# charge_controller.net
KiCad netlist of a schematic drawn in EAGLE
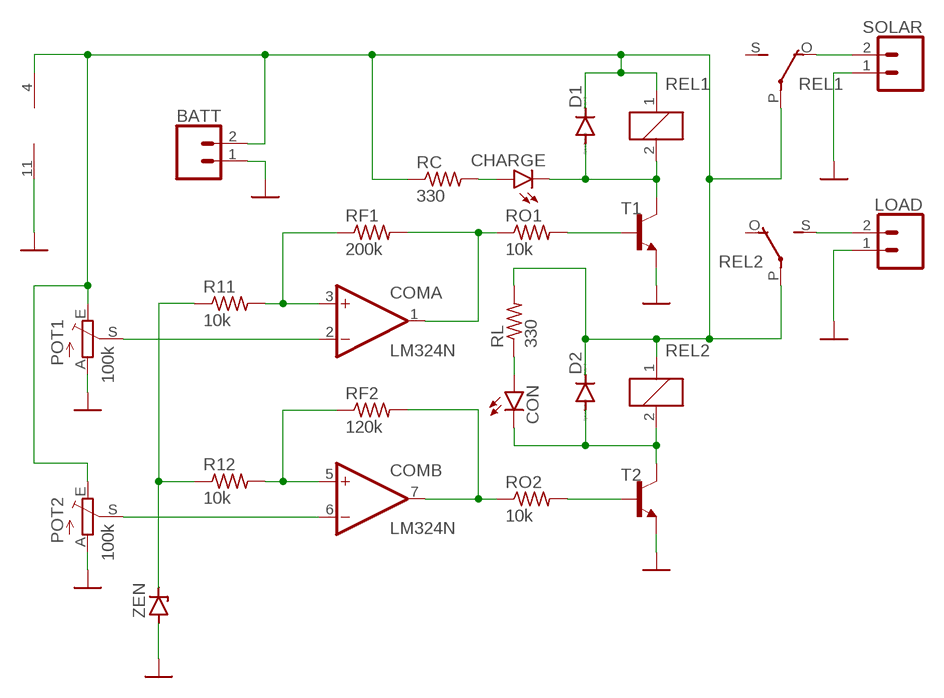
[diagram p0: schematic, sheet 1]

(export (version "E")
  (design (tool "Eeschema 10.0.6"))
  (components
    (comp (ref "BATT")
      (value "CONN_02PTH4")
      (footprint "eagle-import:1X02_XTRA_BIG")
      (libsource (lib "eagle-import") (part "CONN_02PTH4"))
    )
    (comp (ref "CHARGE")
      (value "LED5MM")
      (footprint "eagle-import:LED5MM")
      (libsource (lib "eagle-import") (part "LED5MM"))
    )
    (comp (ref "COM")
      (value "LM324N")
      (footprint "eagle-import:DIL14")
      (libsource (lib "eagle-import") (part "LM324N"))
    )
    (comp (ref "CON")
      (value "LED5MM")
      (footprint "eagle-import:LED5MM")
      (libsource (lib "eagle-import") (part "LED5MM"))
    )
    (comp (ref "D1")
      (value "1N4148DO35-7")
      (footprint "eagle-import:DO35-7")
      (libsource (lib "eagle-import") (part "1N4148DO35-7"))
    )
    (comp (ref "D2")
      (value "1N4148DO35-7")
      (footprint "eagle-import:DO35-7")
      (libsource (lib "eagle-import") (part "1N4148DO35-7"))
    )
    (comp (ref "LOAD")
      (value "CONN_02PTH4")
      (footprint "eagle-import:1X02_XTRA_BIG")
      (libsource (lib "eagle-import") (part "CONN_02PTH4"))
    )
    (comp (ref "POT1")
      (value "100k")
      (footprint "eagle-import:CT6")
      (libsource (lib "eagle-import") (part "TRIM_EU-CT6"))
    )
    (comp (ref "POT2")
      (value "100k")
      (footprint "eagle-import:CT6")
      (libsource (lib "eagle-import") (part "TRIM_EU-CT6"))
    )
    (comp (ref "R11")
      (value "10k")
      (footprint "eagle-import:0207_10")
      (libsource (lib "eagle-import") (part "R-US_0207/10"))
    )
    (comp (ref "R12")
      (value "10k")
      (footprint "eagle-import:0207_10")
      (libsource (lib "eagle-import") (part "R-US_0207/10"))
    )
    (comp (ref "RC")
      (value "330")
      (footprint "eagle-import:0207_10")
      (libsource (lib "eagle-import") (part "R-US_0207/10"))
    )
    (comp (ref "REL1")
      (value "G5L")
      (footprint "eagle-import:G5LE")
      (libsource (lib "eagle-import") (part "G5L"))
    )
    (comp (ref "REL2")
      (value "G5L")
      (footprint "eagle-import:G5LE")
      (libsource (lib "eagle-import") (part "G5L"))
    )
    (comp (ref "RF1")
      (value "200k")
      (footprint "eagle-import:0207_10")
      (libsource (lib "eagle-import") (part "R-US_0207/10"))
    )
    (comp (ref "RF2")
      (value "120k")
      (footprint "eagle-import:0207_10")
      (libsource (lib "eagle-import") (part "R-US_0207/10"))
    )
    (comp (ref "RL")
      (value "330")
      (footprint "eagle-import:0207_10")
      (libsource (lib "eagle-import") (part "R-US_0207/10"))
    )
    (comp (ref "RO1")
      (value "10k")
      (footprint "eagle-import:0207_10")
      (libsource (lib "eagle-import") (part "R-US_0207/10"))
    )
    (comp (ref "RO2")
      (value "10k")
      (footprint "eagle-import:0207_10")
      (libsource (lib "eagle-import") (part "R-US_0207/10"))
    )
    (comp (ref "SOLAR")
      (value "CONN_02PTH4")
      (footprint "eagle-import:1X02_XTRA_BIG")
      (libsource (lib "eagle-import") (part "CONN_02PTH4"))
    )
    (comp (ref "T1")
      (value "MPS2222A-NPN-TO92-CBE")
      (footprint "eagle-import:TO92-CBE")
      (libsource (lib "eagle-import") (part "-NPN-TO92-CBEMPS2222A"))
    )
    (comp (ref "T2")
      (value "MPS2222A-NPN-TO92-CBE")
      (footprint "eagle-import:TO92-CBE")
      (libsource (lib "eagle-import") (part "-NPN-TO92-CBEMPS2222A"))
    )
    (comp (ref "ZEN")
      (value "BZD23")
      (footprint "eagle-import:SOD81")
      (libsource (lib "eagle-import") (part "BZD23"))
    )
  )
  (nets
    (net (code "1") (name "GND") (class "Default")
      (node (ref "BATT") (pin "1") (pinfunction "1_1") (pintype "passive"))
      (node (ref "COM") (pin "11") (pinfunction "V-_11") (pintype "power_in"))
      (node (ref "LOAD") (pin "1") (pinfunction "1_1") (pintype "passive"))
      (node (ref "POT1") (pin "A") (pinfunction "A_A") (pintype "passive"))
      (node (ref "POT2") (pin "A") (pinfunction "A_A") (pintype "passive"))
      (node (ref "SOLAR") (pin "1") (pinfunction "1_1") (pintype "passive"))
      (node (ref "T1") (pin "E") (pinfunction "E_E") (pintype "passive"))
      (node (ref "T2") (pin "E") (pinfunction "E_E") (pintype "passive"))
      (node (ref "ZEN") (pin "A") (pinfunction "A_A") (pintype "passive"))
    )
    (net (code "2") (name "Net-(CHARGE-C)") (class "Default")
      (node (ref "CHARGE") (pin "K") (pinfunction "C_K") (pintype "passive"))
      (node (ref "D1") (pin "A") (pinfunction "A_A") (pintype "passive"))
      (node (ref "REL1") (pin "2") (pinfunction "2_2") (pintype "passive"))
      (node (ref "T1") (pin "C") (pinfunction "C_C") (pintype "passive"))
    )
    (net (code "3") (name "Net-(CHARGE-PadA)") (class "Default")
      (node (ref "CHARGE") (pin "A") (pinfunction "A_A") (pintype "passive"))
      (node (ref "RC") (pin "2") (pinfunction "2_2") (pintype "passive"))
    )
    (net (code "4") (name "Net-(COMA-+IN)") (class "Default")
      (node (ref "COM") (pin "3") (pinfunction "+IN_3") (pintype "input"))
      (node (ref "R11") (pin "2") (pinfunction "2_2") (pintype "passive"))
      (node (ref "RF1") (pin "1") (pinfunction "1_1") (pintype "passive"))
    )
    (net (code "5") (name "Net-(COMA--IN)") (class "Default")
      (node (ref "COM") (pin "2") (pinfunction "-IN_2") (pintype "input"))
      (node (ref "POT1") (pin "S") (pinfunction "S_S") (pintype "passive"))
    )
    (net (code "6") (name "Net-(COMA-OUT)") (class "Default")
      (node (ref "COM") (pin "1") (pinfunction "OUT_1") (pintype "output"))
      (node (ref "RF1") (pin "2") (pinfunction "2_2") (pintype "passive"))
      (node (ref "RO1") (pin "1") (pinfunction "1_1") (pintype "passive"))
    )
    (net (code "7") (name "Net-(COMB-+IN)") (class "Default")
      (node (ref "COM") (pin "5") (pinfunction "+IN_5") (pintype "input"))
      (node (ref "R12") (pin "2") (pinfunction "2_2") (pintype "passive"))
      (node (ref "RF2") (pin "1") (pinfunction "1_1") (pintype "passive"))
    )
    (net (code "8") (name "Net-(COMB--IN)") (class "Default")
      (node (ref "COM") (pin "6") (pinfunction "-IN_6") (pintype "input"))
      (node (ref "POT2") (pin "S") (pinfunction "S_S") (pintype "passive"))
    )
    (net (code "9") (name "Net-(COMB-OUT)") (class "Default")
      (node (ref "COM") (pin "7") (pinfunction "OUT_7") (pintype "output"))
      (node (ref "RF2") (pin "2") (pinfunction "2_2") (pintype "passive"))
      (node (ref "RO2") (pin "1") (pinfunction "1_1") (pintype "passive"))
    )
    (net (code "10") (name "Net-(COME-V+)") (class "Default")
      (node (ref "BATT") (pin "2") (pinfunction "2_2") (pintype "passive"))
      (node (ref "COM") (pin "4") (pinfunction "V+_4") (pintype "power_in"))
      (node (ref "D1") (pin "C") (pinfunction "C_C") (pintype "passive"))
      (node (ref "D2") (pin "C") (pinfunction "C_C") (pintype "passive"))
      (node (ref "POT1") (pin "E") (pinfunction "E_E") (pintype "passive"))
      (node (ref "POT2") (pin "E") (pinfunction "E_E") (pintype "passive"))
      (node (ref "RC") (pin "1") (pinfunction "1_1") (pintype "passive"))
      (node (ref "REL1") (pin "1") (pinfunction "1_1") (pintype "passive"))
      (node (ref "REL1") (pin "P") (pinfunction "P_P") (pintype "passive"))
      (node (ref "REL2") (pin "1") (pinfunction "1_1") (pintype "passive"))
      (node (ref "REL2") (pin "P") (pinfunction "P_P") (pintype "passive"))
      (node (ref "RL") (pin "2") (pinfunction "2_2") (pintype "passive"))
    )
    (net (code "11") (name "Net-(CON-C)") (class "Default")
      (node (ref "CON") (pin "K") (pinfunction "C_K") (pintype "passive"))
      (node (ref "D2") (pin "A") (pinfunction "A_A") (pintype "passive"))
      (node (ref "REL2") (pin "2") (pinfunction "2_2") (pintype "passive"))
      (node (ref "T2") (pin "C") (pinfunction "C_C") (pintype "passive"))
    )
    (net (code "12") (name "Net-(CON-PadA)") (class "Default")
      (node (ref "CON") (pin "A") (pinfunction "A_A") (pintype "passive"))
      (node (ref "RL") (pin "1") (pinfunction "1_1") (pintype "passive"))
    )
    (net (code "13") (name "Net-(LOAD-Pad2)") (class "Default")
      (node (ref "LOAD") (pin "2") (pinfunction "2_2") (pintype "passive"))
      (node (ref "REL2") (pin "S") (pinfunction "S_S") (pintype "passive"))
    )
    (net (code "14") (name "Net-(R11-Pad1)") (class "Default")
      (node (ref "R11") (pin "1") (pinfunction "1_1") (pintype "passive"))
      (node (ref "R12") (pin "1") (pinfunction "1_1") (pintype "passive"))
      (node (ref "ZEN") (pin "C") (pinfunction "C_C") (pintype "passive"))
    )
    (net (code "15") (name "Net-(REL1-PadO)") (class "Default")
      (node (ref "REL1") (pin "O") (pinfunction "O_O") (pintype "passive"))
      (node (ref "SOLAR") (pin "2") (pinfunction "2_2") (pintype "passive"))
    )
    (net (code "16") (name "Net-(RO1-Pad2)") (class "Default")
      (node (ref "RO1") (pin "2") (pinfunction "2_2") (pintype "passive"))
      (node (ref "T1") (pin "B") (pinfunction "B_B") (pintype "passive"))
    )
    (net (code "17") (name "Net-(RO2-Pad2)") (class "Default")
      (node (ref "RO2") (pin "2") (pinfunction "2_2") (pintype "passive"))
      (node (ref "T2") (pin "B") (pinfunction "B_B") (pintype "passive"))
    )
    (net (code "18") (name "unconnected-(REL1-PadS)") (class "Default")
      (node (ref "REL1") (pin "S") (pinfunction "S_S") (pintype "passive"))
    )
    (net (code "19") (name "unconnected-(REL2-PadO)") (class "Default")
      (node (ref "REL2") (pin "O") (pinfunction "O_O") (pintype "passive"))
    )
  )
)
